# 3DA_V2.net
KiCad netlist of a schematic drawn in EAGLE
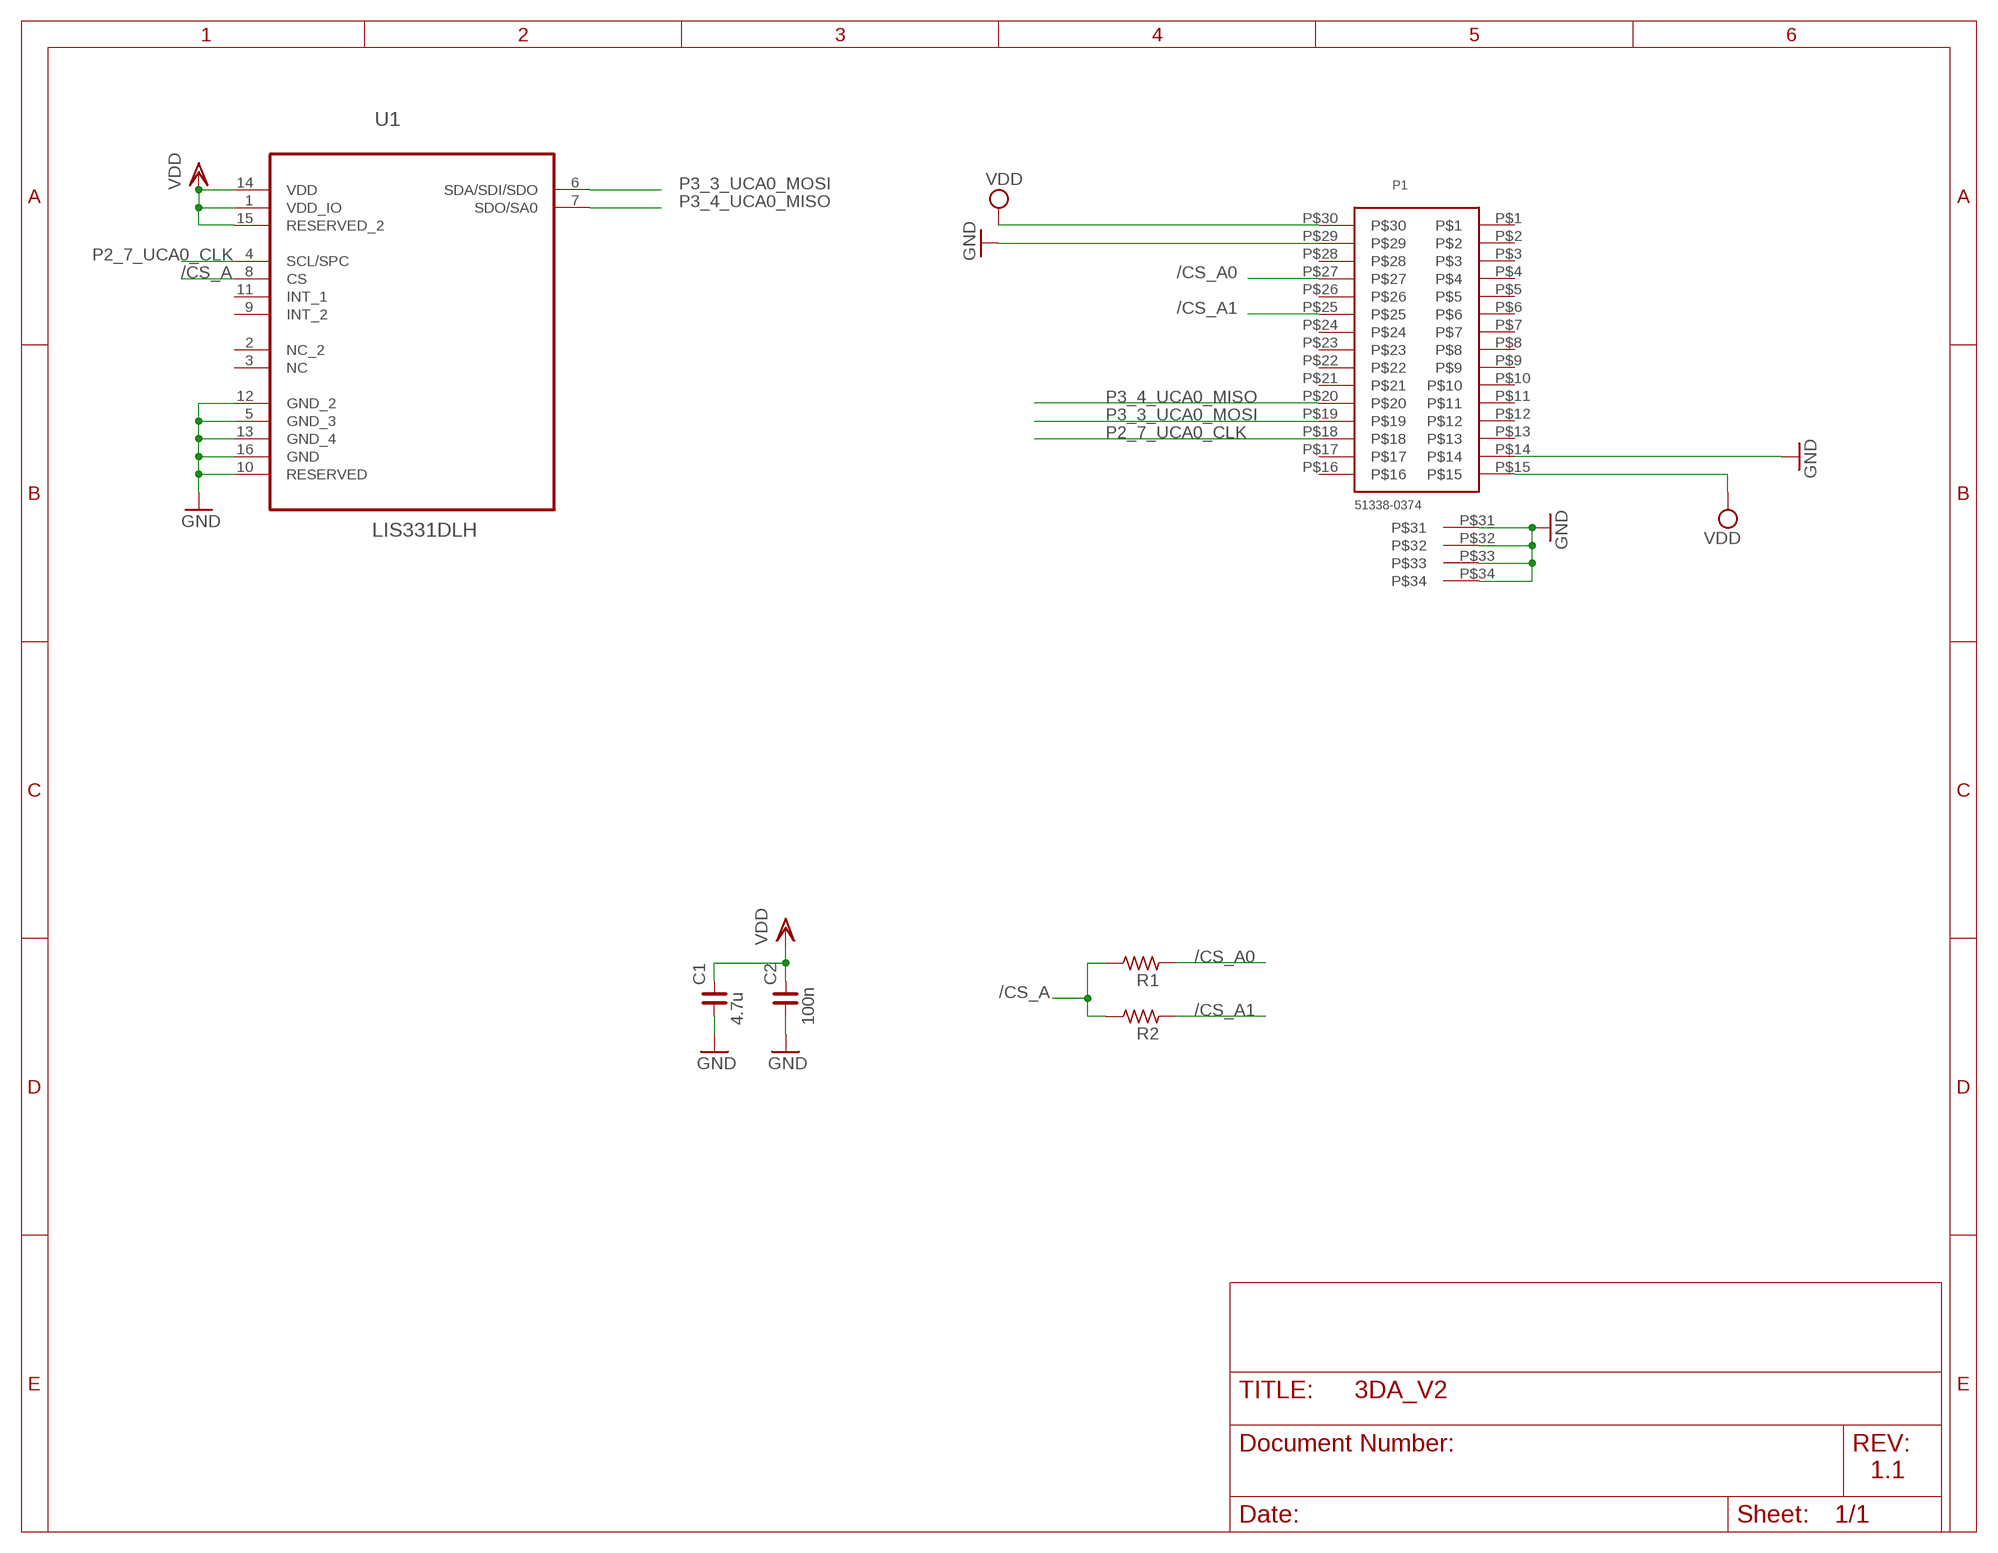
[diagram p0: schematic, sheet 1]

(export (version "E")
  (design (tool "Eeschema 10.0.6"))
  (components
    (comp (ref "C1")
      (value "4.7u")
      (footprint "eagle-import:C0402")
      (libsource (lib "eagle-import") (part "C_0402"))
    )
    (comp (ref "C2")
      (value "100n")
      (footprint "eagle-import:C0402")
      (libsource (lib "eagle-import") (part "C_0402"))
    )
    (comp (ref "P1")
      (value "51338-0374")
      (footprint "eagle-import:51338-0374_RECEPTACLE")
      (libsource (lib "eagle-import") (part "51338-0374_RECEPTACLE"))
    )
    (comp (ref "R1")
      (value "R_0402")
      (footprint "eagle-import:R0402")
      (libsource (lib "eagle-import") (part "R_0402"))
    )
    (comp (ref "R2")
      (value "R_0402")
      (footprint "eagle-import:R0402")
      (libsource (lib "eagle-import") (part "R_0402"))
    )
    (comp (ref "U1")
      (value "LIS331DLH")
      (footprint "eagle-import:LGA16R50P3X5_300X300X100")
      (libsource (lib "eagle-import") (part "LIS331DLH"))
    )
  )
  (nets
    (net (code "1") (name "/P2_7_UCA0_CLK") (class "Default")
      (node (ref "P1") (pin "P$18") (pinfunction "P$18_P$18") (pintype "bidirectional"))
      (node (ref "U1") (pin "4") (pinfunction "SCL/SPC_4") (pintype "input"))
    )
    (net (code "2") (name "/P3_3_UCA0_MOSI") (class "Default")
      (node (ref "P1") (pin "P$19") (pinfunction "P$19_P$19") (pintype "bidirectional"))
      (node (ref "U1") (pin "6") (pinfunction "SDA/SDI/SDO_6") (pintype "bidirectional"))
    )
    (net (code "3") (name "/P3_4_UCA0_MISO") (class "Default")
      (node (ref "P1") (pin "P$20") (pinfunction "P$20_P$20") (pintype "bidirectional"))
      (node (ref "U1") (pin "7") (pinfunction "SDO/SA0_7") (pintype "output"))
    )
    (net (code "4") (name "/{slash}CS_A") (class "Default")
      (node (ref "R1") (pin "2") (pinfunction "2_2") (pintype "passive"))
      (node (ref "R2") (pin "2") (pinfunction "2_2") (pintype "passive"))
      (node (ref "U1") (pin "8") (pinfunction "CS_8") (pintype "input"))
    )
    (net (code "5") (name "/{slash}CS_A0") (class "Default")
      (node (ref "P1") (pin "P$27") (pinfunction "P$27_P$27") (pintype "bidirectional"))
      (node (ref "R1") (pin "1") (pinfunction "1_1") (pintype "passive"))
    )
    (net (code "6") (name "/{slash}CS_A1") (class "Default")
      (node (ref "P1") (pin "P$25") (pinfunction "P$25_P$25") (pintype "bidirectional"))
      (node (ref "R2") (pin "1") (pinfunction "1_1") (pintype "passive"))
    )
    (net (code "7") (name "GND") (class "Default")
      (node (ref "C1") (pin "1") (pinfunction "1_1") (pintype "passive"))
      (node (ref "C2") (pin "1") (pinfunction "1_1") (pintype "passive"))
      (node (ref "P1") (pin "P$14") (pinfunction "P$14_P$14") (pintype "bidirectional"))
      (node (ref "P1") (pin "P$29") (pinfunction "P$29_P$29") (pintype "bidirectional"))
      (node (ref "P1") (pin "P$31") (pinfunction "P$31_P$31") (pintype "bidirectional"))
      (node (ref "P1") (pin "P$32") (pinfunction "P$32_P$32") (pintype "bidirectional"))
      (node (ref "P1") (pin "P$33") (pinfunction "P$33_P$33") (pintype "bidirectional"))
      (node (ref "P1") (pin "P$34") (pinfunction "P$34_P$34") (pintype "bidirectional"))
      (node (ref "U1") (pin "10") (pinfunction "RESERVED_10") (pintype "passive"))
      (node (ref "U1") (pin "12") (pinfunction "GND_2_12") (pintype "passive"))
      (node (ref "U1") (pin "13") (pinfunction "GND_4_13") (pintype "passive"))
      (node (ref "U1") (pin "16") (pinfunction "GND_16") (pintype "passive"))
      (node (ref "U1") (pin "5") (pinfunction "GND_3_5") (pintype "passive"))
    )
    (net (code "8") (name "VDD") (class "Default")
      (node (ref "C1") (pin "2") (pinfunction "2_2") (pintype "passive"))
      (node (ref "C2") (pin "2") (pinfunction "2_2") (pintype "passive"))
      (node (ref "P1") (pin "P$15") (pinfunction "P$15_P$15") (pintype "bidirectional"))
      (node (ref "P1") (pin "P$30") (pinfunction "P$30_P$30") (pintype "bidirectional"))
      (node (ref "U1") (pin "1") (pinfunction "VDD_IO_1") (pintype "power_in"))
      (node (ref "U1") (pin "14") (pinfunction "VDD_14") (pintype "power_in"))
      (node (ref "U1") (pin "15") (pinfunction "RESERVED_2_15") (pintype "power_in"))
    )
    (net (code "9") (name "unconnected-(P1-PadP$1)") (class "Default")
      (node (ref "P1") (pin "P$1") (pinfunction "P$1_P$1") (pintype "bidirectional"))
    )
    (net (code "10") (name "unconnected-(P1-PadP$2)") (class "Default")
      (node (ref "P1") (pin "P$2") (pinfunction "P$2_P$2") (pintype "bidirectional"))
    )
    (net (code "11") (name "unconnected-(P1-PadP$3)") (class "Default")
      (node (ref "P1") (pin "P$3") (pinfunction "P$3_P$3") (pintype "bidirectional"))
    )
    (net (code "12") (name "unconnected-(P1-PadP$4)") (class "Default")
      (node (ref "P1") (pin "P$4") (pinfunction "P$4_P$4") (pintype "bidirectional"))
    )
    (net (code "13") (name "unconnected-(P1-PadP$5)") (class "Default")
      (node (ref "P1") (pin "P$5") (pinfunction "P$5_P$5") (pintype "bidirectional"))
    )
    (net (code "14") (name "unconnected-(P1-PadP$6)") (class "Default")
      (node (ref "P1") (pin "P$6") (pinfunction "P$6_P$6") (pintype "bidirectional"))
    )
    (net (code "15") (name "unconnected-(P1-PadP$7)") (class "Default")
      (node (ref "P1") (pin "P$7") (pinfunction "P$7_P$7") (pintype "bidirectional"))
    )
    (net (code "16") (name "unconnected-(P1-PadP$8)") (class "Default")
      (node (ref "P1") (pin "P$8") (pinfunction "P$8_P$8") (pintype "bidirectional"))
    )
    (net (code "17") (name "unconnected-(P1-PadP$9)") (class "Default")
      (node (ref "P1") (pin "P$9") (pinfunction "P$9_P$9") (pintype "bidirectional"))
    )
    (net (code "18") (name "unconnected-(P1-PadP$10)") (class "Default")
      (node (ref "P1") (pin "P$10") (pinfunction "P$10_P$10") (pintype "bidirectional"))
    )
    (net (code "19") (name "unconnected-(P1-PadP$11)") (class "Default")
      (node (ref "P1") (pin "P$11") (pinfunction "P$11_P$11") (pintype "bidirectional"))
    )
    (net (code "20") (name "unconnected-(P1-PadP$12)") (class "Default")
      (node (ref "P1") (pin "P$12") (pinfunction "P$12_P$12") (pintype "bidirectional"))
    )
    (net (code "21") (name "unconnected-(P1-PadP$13)") (class "Default")
      (node (ref "P1") (pin "P$13") (pinfunction "P$13_P$13") (pintype "bidirectional"))
    )
    (net (code "22") (name "unconnected-(P1-PadP$16)") (class "Default")
      (node (ref "P1") (pin "P$16") (pinfunction "P$16_P$16") (pintype "bidirectional"))
    )
    (net (code "23") (name "unconnected-(P1-PadP$17)") (class "Default")
      (node (ref "P1") (pin "P$17") (pinfunction "P$17_P$17") (pintype "bidirectional"))
    )
    (net (code "24") (name "unconnected-(P1-PadP$21)") (class "Default")
      (node (ref "P1") (pin "P$21") (pinfunction "P$21_P$21") (pintype "bidirectional"))
    )
    (net (code "25") (name "unconnected-(P1-PadP$22)") (class "Default")
      (node (ref "P1") (pin "P$22") (pinfunction "P$22_P$22") (pintype "bidirectional"))
    )
    (net (code "26") (name "unconnected-(P1-PadP$23)") (class "Default")
      (node (ref "P1") (pin "P$23") (pinfunction "P$23_P$23") (pintype "bidirectional"))
    )
    (net (code "27") (name "unconnected-(P1-PadP$24)") (class "Default")
      (node (ref "P1") (pin "P$24") (pinfunction "P$24_P$24") (pintype "bidirectional"))
    )
    (net (code "28") (name "unconnected-(P1-PadP$26)") (class "Default")
      (node (ref "P1") (pin "P$26") (pinfunction "P$26_P$26") (pintype "bidirectional"))
    )
    (net (code "29") (name "unconnected-(P1-PadP$28)") (class "Default")
      (node (ref "P1") (pin "P$28") (pinfunction "P$28_P$28") (pintype "bidirectional"))
    )
    (net (code "30") (name "unconnected-(U1-INT_1-Pad11)") (class "Default")
      (node (ref "U1") (pin "11") (pinfunction "INT_1_11") (pintype "input"))
    )
    (net (code "31") (name "unconnected-(U1-INT_2-Pad9)") (class "Default")
      (node (ref "U1") (pin "9") (pinfunction "INT_2_9") (pintype "input"))
    )
    (net (code "32") (name "unconnected-(U1-NC-Pad3)") (class "Default")
      (node (ref "U1") (pin "3") (pinfunction "NC_3") (pintype "no_connect"))
    )
    (net (code "33") (name "unconnected-(U1-NC_2-Pad2)") (class "Default")
      (node (ref "U1") (pin "2") (pinfunction "NC_2_2") (pintype "no_connect"))
    )
  )
)
